# PowerDriver.net
KiCad netlist of a schematic drawn in Altium Designer
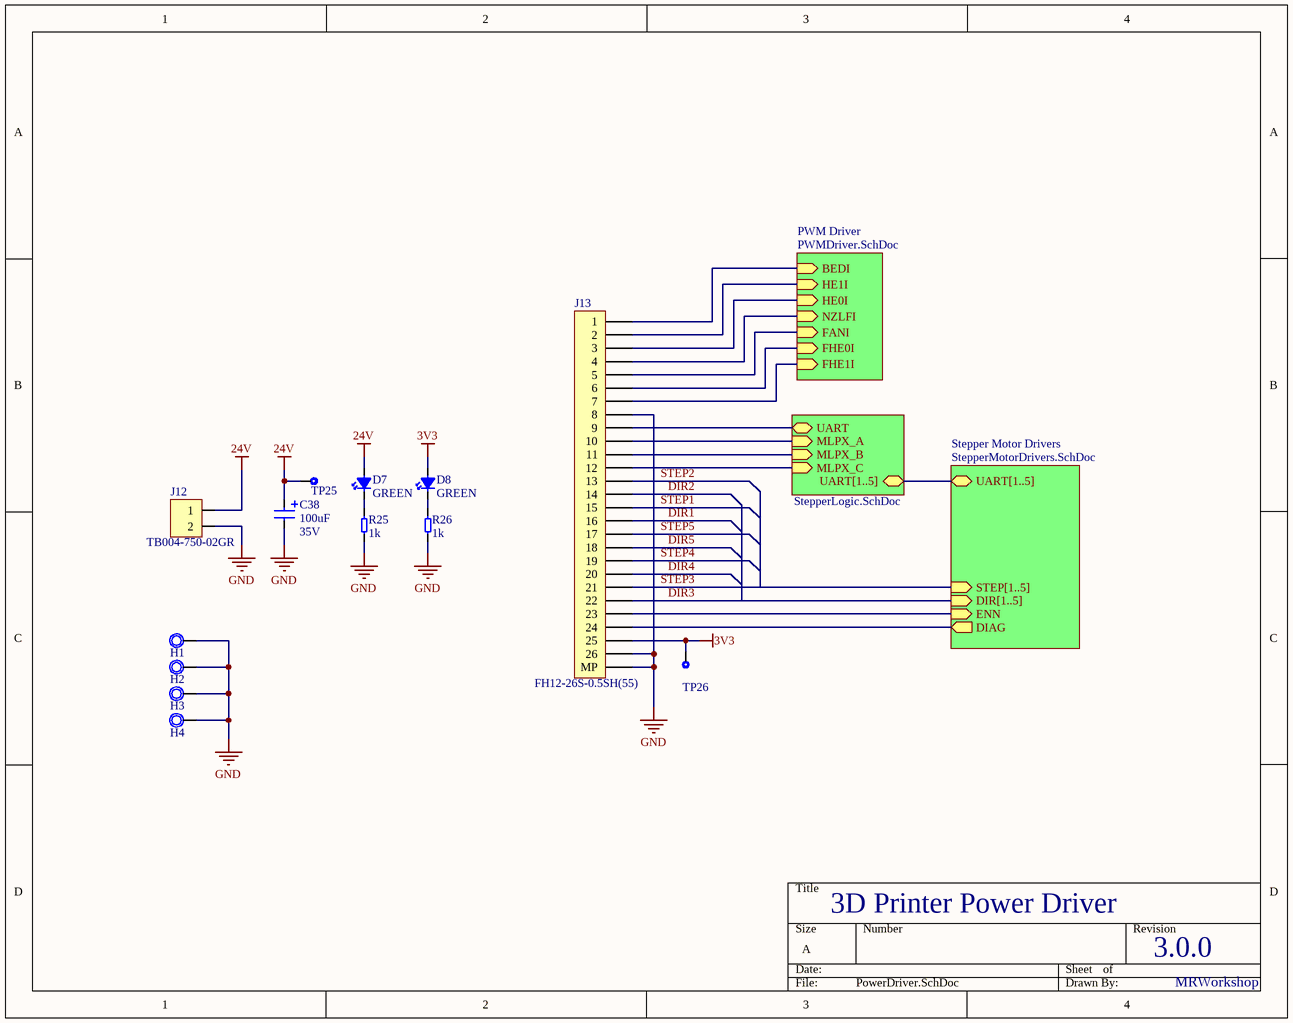
[diagram p0: PowerDriver.SchDoc]

(export (version "E")
  (design (tool "Eeschema 10.0.6"))
  (components
    (comp (ref "C38")
      (value "100uF")
      (footprint "C_8.3x10.5")
      (description "Aluminum Electrolytic Capacitors - SMD 35V 100uF 20% AEC-Q200")
      (fields (field (name "VOLTAGE") "35V") (field (name "Comment") "EDT107M035S9MAA"))
      (libsource (lib "Capacitors") (part "EDT107M035S9MAA"))
    )
    (comp (ref "D7")
      (value "GREEN")
      (footprint "LED_0402")
      (description "Single Colour LEDs GREEN WTR CLEAR 40mcd 574nm")
      (libsource (lib "LEDs") (part "APHHS1005CGCK"))
    )
    (comp (ref "D8")
      (value "GREEN")
      (footprint "LED_0402")
      (description "Single Colour LEDs GREEN WTR CLEAR 40mcd 574nm")
      (libsource (lib "LEDs") (part "APHHS1005CGCK"))
    )
    (comp (ref "H1")
      (value "Mounting_Hole_M3")
      (footprint "M3")
      (libsource (lib "Misc") (part "Mounting_Hole_M3"))
    )
    (comp (ref "H2")
      (value "Mounting_Hole_M3")
      (footprint "M3")
      (libsource (lib "Misc") (part "Mounting_Hole_M3"))
    )
    (comp (ref "H3")
      (value "Mounting_Hole_M3")
      (footprint "M3")
      (libsource (lib "Misc") (part "Mounting_Hole_M3"))
    )
    (comp (ref "H4")
      (value "Mounting_Hole_M3")
      (footprint "M3")
      (libsource (lib "Misc") (part "Mounting_Hole_M3"))
    )
    (comp (ref "J12")
      (value "TB004-750-02GR")
      (footprint "TB004-750-02GR")
      (description "Fixed Terminal Blocks 2 Poles, Screw Type, Horizontal, 7.50 mm Pitch, 24-12 (AWG)")
      (libsource (lib "Connectors") (part "TB004-750-02GR"))
    )
    (comp (ref "J13")
      (value "FH12-26S-0.5SH(55)")
      (footprint "FH12-26S-0.5SH(55)")
      (description "FFC & FPC Connectors 0.5MM 26 POS R/A BTTM SMT GLD")
      (libsource (lib "Connectors") (part "FH12-26S-0.5SH(55)"))
    )
    (comp (ref "R25")
      (value "1k")
      (footprint "R_0402")
      (description "Thick Film Resistors - SMD 1.0K OHM 1%")
      (fields (field (name "TOLERANCE") "1%") (field (name "POWER") "62.5mW"))
      (libsource (lib "Resistors") (part "CR0402-FX-1001GLF"))
    )
    (comp (ref "R26")
      (value "1k")
      (footprint "R_0402")
      (description "Thick Film Resistors - SMD 1.0K OHM 1%")
      (fields (field (name "TOLERANCE") "1%") (field (name "POWER") "62.5mW"))
      (libsource (lib "Resistors") (part "CR0402-FX-1001GLF"))
    )
    (comp (ref "TP25")
      (value "TestPoint_1mm")
      (footprint "TestPoint_1mm")
      (libsource (lib "Misc") (part "TestPoint_1mm"))
    )
    (comp (ref "TP26")
      (value "TestPoint_1mm")
      (footprint "TestPoint_1mm")
      (libsource (lib "Misc") (part "TestPoint_1mm"))
    )
  )
  (nets
    (net (code "1") (name "/BEDI") (class "Default")
      (node (ref "J13") (pin "1") (pinfunction "1_1") (pintype "passive"))
    )
    (net (code "2") (name "/DIAG") (class "Default")
      (node (ref "J13") (pin "24") (pinfunction "24_24") (pintype "passive"))
    )
    (net (code "3") (name "/DIR1") (class "Default")
      (node (ref "J13") (pin "16") (pinfunction "16_16") (pintype "passive"))
    )
    (net (code "4") (name "/DIR2") (class "Default")
      (node (ref "J13") (pin "14") (pinfunction "14_14") (pintype "passive"))
    )
    (net (code "5") (name "/DIR3") (class "Default")
      (node (ref "J13") (pin "22") (pinfunction "22_22") (pintype "passive"))
    )
    (net (code "6") (name "/DIR4") (class "Default")
      (node (ref "J13") (pin "20") (pinfunction "20_20") (pintype "passive"))
    )
    (net (code "7") (name "/DIR5") (class "Default")
      (node (ref "J13") (pin "18") (pinfunction "18_18") (pintype "passive"))
    )
    (net (code "9") (name "/ENN") (class "Default")
      (node (ref "J13") (pin "23") (pinfunction "23_23") (pintype "passive"))
    )
    (net (code "10") (name "/FANI") (class "Default")
      (node (ref "J13") (pin "5") (pinfunction "5_5") (pintype "passive"))
    )
    (net (code "11") (name "/FHE0I") (class "Default")
      (node (ref "J13") (pin "6") (pinfunction "6_6") (pintype "passive"))
    )
    (net (code "12") (name "/FHE1I") (class "Default")
      (node (ref "J13") (pin "7") (pinfunction "7_7") (pintype "passive"))
    )
    (net (code "13") (name "/HE0I") (class "Default")
      (node (ref "J13") (pin "3") (pinfunction "3_3") (pintype "passive"))
    )
    (net (code "14") (name "/HE1I") (class "Default")
      (node (ref "J13") (pin "2") (pinfunction "2_2") (pintype "passive"))
    )
    (net (code "15") (name "/MLPX_A") (class "Default")
      (node (ref "J13") (pin "10") (pinfunction "10_10") (pintype "passive"))
    )
    (net (code "16") (name "/MLPX_B") (class "Default")
      (node (ref "J13") (pin "11") (pinfunction "11_11") (pintype "passive"))
    )
    (net (code "17") (name "/MLPX_C") (class "Default")
      (node (ref "J13") (pin "12") (pinfunction "12_12") (pintype "passive"))
    )
    (net (code "18") (name "/NZLFI") (class "Default")
      (node (ref "J13") (pin "4") (pinfunction "4_4") (pintype "passive"))
    )
    (net (code "19") (name "/STEP1") (class "Default")
      (node (ref "J13") (pin "15") (pinfunction "15_15") (pintype "passive"))
    )
    (net (code "20") (name "/STEP2") (class "Default")
      (node (ref "J13") (pin "13") (pinfunction "13_13") (pintype "passive"))
    )
    (net (code "21") (name "/STEP3") (class "Default")
      (node (ref "J13") (pin "21") (pinfunction "21_21") (pintype "passive"))
    )
    (net (code "22") (name "/STEP4") (class "Default")
      (node (ref "J13") (pin "19") (pinfunction "19_19") (pintype "passive"))
    )
    (net (code "23") (name "/STEP5") (class "Default")
      (node (ref "J13") (pin "17") (pinfunction "17_17") (pintype "passive"))
    )
    (net (code "25") (name "/UART") (class "Default")
      (node (ref "J13") (pin "9") (pinfunction "9_9") (pintype "passive"))
    )
    (net (code "27") (name "3V3") (class "Default")
      (node (ref "D8") (pin "2") (pinfunction "2_2") (pintype "passive"))
      (node (ref "J13") (pin "25") (pinfunction "25_25") (pintype "passive"))
      (node (ref "TP26") (pin "1") (pinfunction "1_1") (pintype "passive"))
    )
    (net (code "28") (name "24V") (class "Default")
      (node (ref "C38") (pin "1") (pinfunction "1_1") (pintype "passive"))
      (node (ref "D7") (pin "2") (pinfunction "2_2") (pintype "passive"))
      (node (ref "J12") (pin "1") (pinfunction "1_1") (pintype "passive"))
      (node (ref "TP25") (pin "1") (pinfunction "1_1") (pintype "passive"))
    )
    (net (code "29") (name "GND") (class "Default")
      (node (ref "C38") (pin "2") (pinfunction "2_2") (pintype "passive"))
      (node (ref "H1") (pin "1") (pinfunction "1_1") (pintype "passive"))
      (node (ref "H2") (pin "1") (pinfunction "1_1") (pintype "passive"))
      (node (ref "H3") (pin "1") (pinfunction "1_1") (pintype "passive"))
      (node (ref "H4") (pin "1") (pinfunction "1_1") (pintype "passive"))
      (node (ref "J12") (pin "2") (pinfunction "2_2") (pintype "passive"))
      (node (ref "J13") (pin "0") (pinfunction "MP_0") (pintype "passive"))
      (node (ref "J13") (pin "26") (pinfunction "26_26") (pintype "passive"))
      (node (ref "J13") (pin "8") (pinfunction "8_8") (pintype "passive"))
      (node (ref "R25") (pin "1") (pinfunction "1_1") (pintype "passive"))
      (node (ref "R26") (pin "1") (pinfunction "1_1") (pintype "passive"))
    )
    (net (code "30") (name "Net-(D7-Pad1)") (class "Default")
      (node (ref "D7") (pin "1") (pinfunction "1_1") (pintype "passive"))
      (node (ref "R25") (pin "2") (pinfunction "2_2") (pintype "passive"))
    )
    (net (code "31") (name "Net-(D8-Pad1)") (class "Default")
      (node (ref "D8") (pin "1") (pinfunction "1_1") (pintype "passive"))
      (node (ref "R26") (pin "2") (pinfunction "2_2") (pintype "passive"))
    )
  )
)
